# Empty_Shield-v13.net
KiCad netlist of a schematic drawn in EAGLE
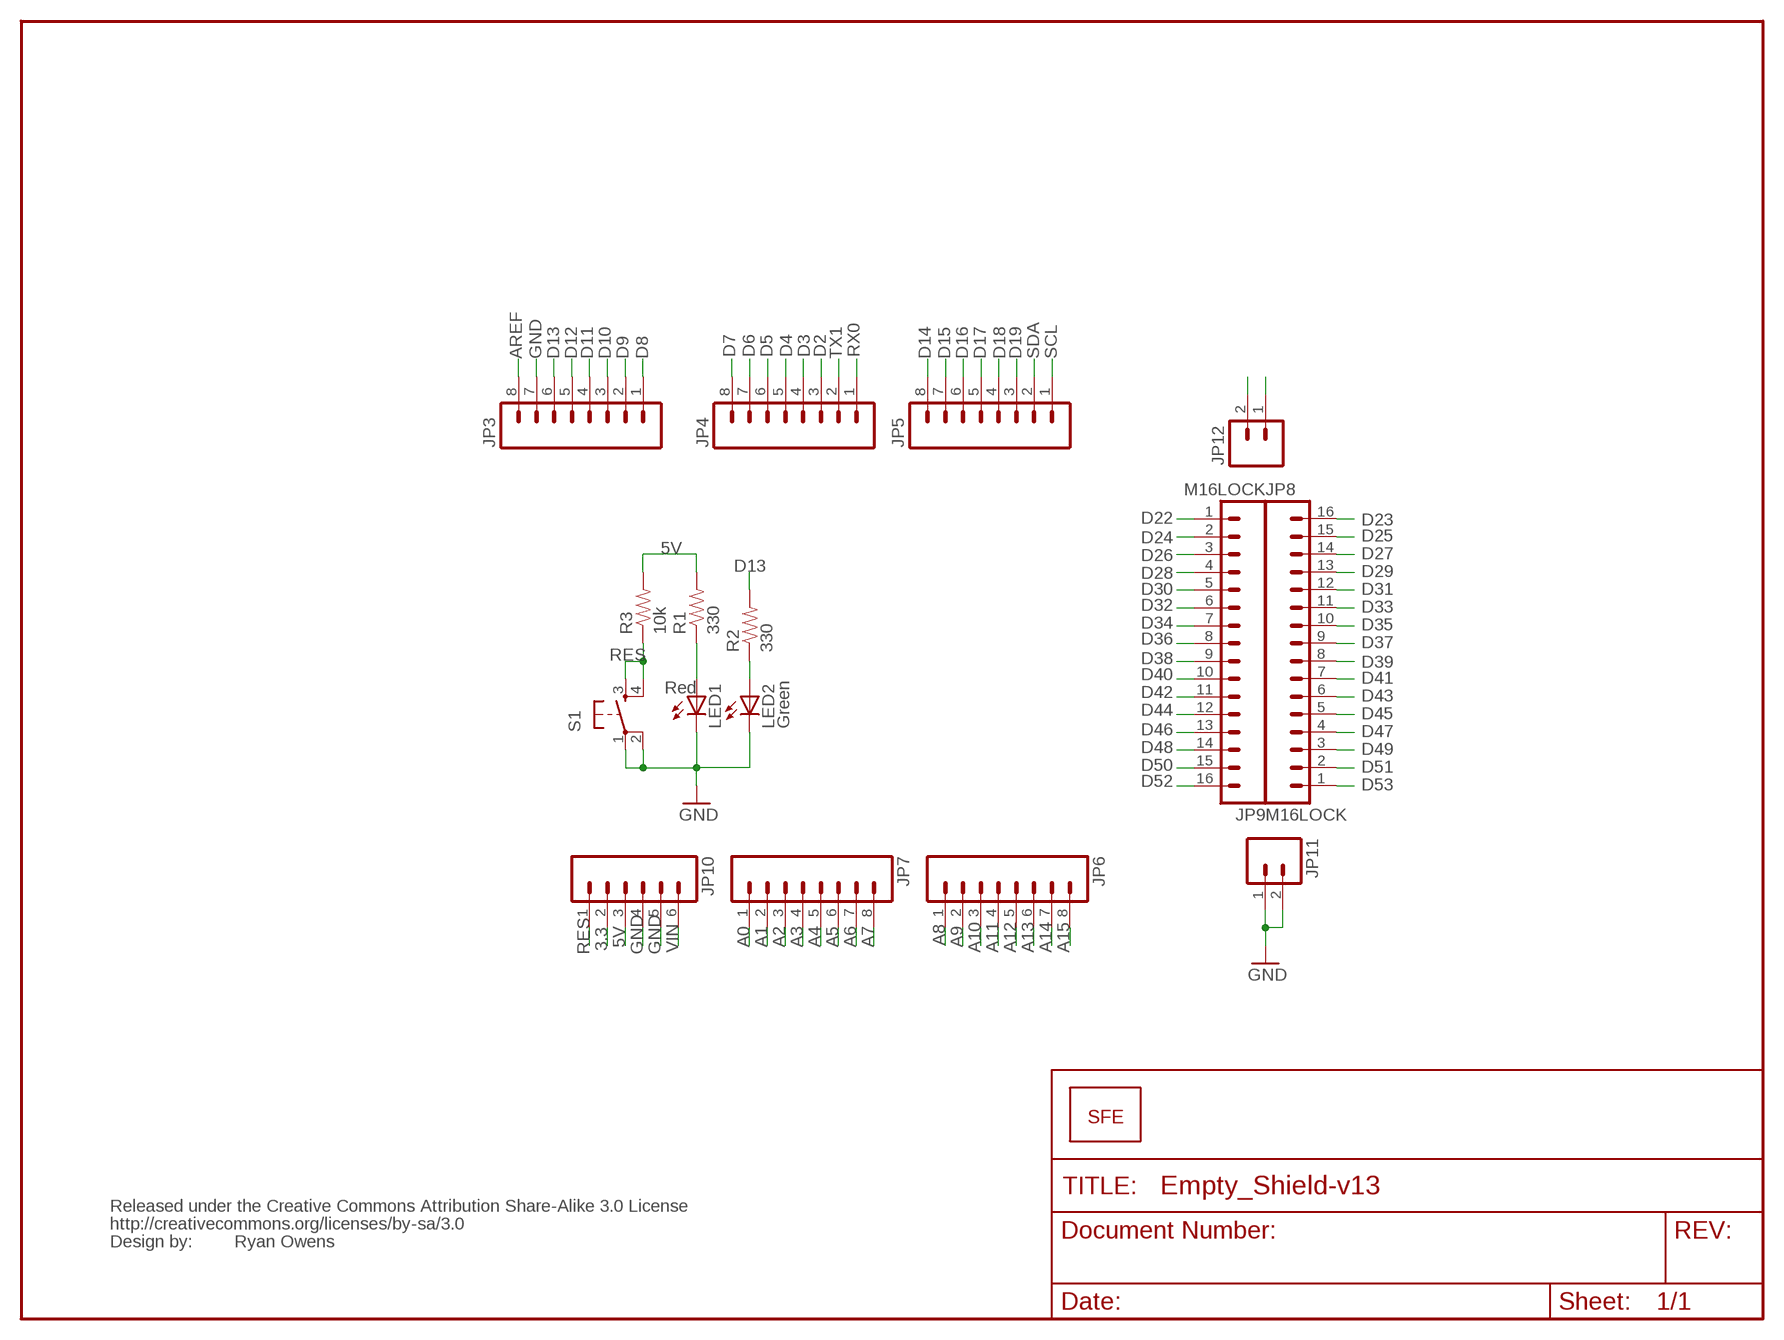
[diagram p0: schematic, sheet 1]

(export (version "E")
  (design (tool "Eeschema 10.0.6"))
  (components
    (comp (ref "JP3")
      (value "M08LOCK")
      (footprint "eagle-import:1X08_LOCK")
      (libsource (lib "eagle-import") (part "M08LOCK"))
    )
    (comp (ref "JP4")
      (value "M08LOCK")
      (footprint "eagle-import:1X08_LOCK")
      (libsource (lib "eagle-import") (part "M08LOCK"))
    )
    (comp (ref "JP5")
      (value "M08LOCK")
      (footprint "eagle-import:1X08_LOCK")
      (libsource (lib "eagle-import") (part "M08LOCK"))
    )
    (comp (ref "JP6")
      (value "M08LOCK")
      (footprint "eagle-import:1X08_LOCK")
      (libsource (lib "eagle-import") (part "M08LOCK"))
    )
    (comp (ref "JP7")
      (value "M08LOCK")
      (footprint "eagle-import:1X08_LOCK")
      (libsource (lib "eagle-import") (part "M08LOCK"))
    )
    (comp (ref "JP8")
      (value "M16LOCK")
      (footprint "eagle-import:1X16_LOCK")
      (libsource (lib "eagle-import") (part "M16LOCK"))
    )
    (comp (ref "JP9")
      (value "M16LOCK")
      (footprint "eagle-import:1X16_LOCK")
      (libsource (lib "eagle-import") (part "M16LOCK"))
    )
    (comp (ref "JP10")
      (value "M06LOCK")
      (footprint "eagle-import:1X06_LOCK")
      (libsource (lib "eagle-import") (part "M06LOCK"))
    )
    (comp (ref "JP11")
      (value "M02LOCK")
      (footprint "eagle-import:1X02_LOCK")
      (libsource (lib "eagle-import") (part "M02LOCK"))
    )
    (comp (ref "JP12")
      (value "M02LOCK")
      (footprint "eagle-import:1X02_LOCK")
      (libsource (lib "eagle-import") (part "M02LOCK"))
    )
    (comp (ref "LED1")
      (value "Red")
      (footprint "eagle-import:LED5MM")
      (libsource (lib "eagle-import") (part "LED5MM"))
    )
    (comp (ref "LED2")
      (value "Green")
      (footprint "eagle-import:LED5MM")
      (libsource (lib "eagle-import") (part "LED5MM"))
    )
    (comp (ref "R1")
      (value "330")
      (footprint "eagle-import:AXIAL-0.3")
      (libsource (lib "eagle-import") (part "RESISTORPTH1"))
    )
    (comp (ref "R2")
      (value "330")
      (footprint "eagle-import:AXIAL-0.3")
      (libsource (lib "eagle-import") (part "RESISTORPTH1"))
    )
    (comp (ref "R3")
      (value "10k")
      (footprint "eagle-import:AXIAL-0.3")
      (libsource (lib "eagle-import") (part "RESISTORPTH1"))
    )
    (comp (ref "S1")
      (value "TAC_SWITCHPTH")
      (footprint "eagle-import:TACTILE-PTH")
      (libsource (lib "eagle-import") (part "TAC_SWITCHPTH"))
    )
    (comp (ref "U$1")
      (value "LOGO-SFENEW")
      (footprint "eagle-import:SFE-NEW-WEBLOGO")
      (libsource (lib "eagle-import") (part "LOGO-SFENEW"))
    )
    (comp (ref "U$2")
      (value "CREATIVE_COMMONS")
      (footprint "eagle-import:CREATIVE_COMMONS")
      (libsource (lib "eagle-import") (part "CREATIVE_COMMONS"))
    )
  )
  (nets
    (net (code "1") (name "/3.3") (class "Default")
      (node (ref "JP10") (pin "2") (pinfunction "2_2") (pintype "passive"))
    )
    (net (code "2") (name "/5V") (class "Default")
      (node (ref "JP10") (pin "3") (pinfunction "3_3") (pintype "passive"))
      (node (ref "R1") (pin "P$2") (pinfunction "2_P$2") (pintype "passive"))
      (node (ref "R3") (pin "P$2") (pinfunction "2_P$2") (pintype "passive"))
    )
    (net (code "3") (name "/5V@1") (class "Default")
      (node (ref "JP12") (pin "1") (pinfunction "1_1") (pintype "passive"))
      (node (ref "JP12") (pin "2") (pinfunction "2_2") (pintype "passive"))
    )
    (net (code "4") (name "/A0") (class "Default")
      (node (ref "JP7") (pin "1") (pinfunction "1_1") (pintype "passive"))
    )
    (net (code "5") (name "/A1") (class "Default")
      (node (ref "JP7") (pin "2") (pinfunction "2_2") (pintype "passive"))
    )
    (net (code "6") (name "/A2") (class "Default")
      (node (ref "JP7") (pin "3") (pinfunction "3_3") (pintype "passive"))
    )
    (net (code "7") (name "/A3") (class "Default")
      (node (ref "JP7") (pin "4") (pinfunction "4_4") (pintype "passive"))
    )
    (net (code "8") (name "/A4") (class "Default")
      (node (ref "JP7") (pin "5") (pinfunction "5_5") (pintype "passive"))
    )
    (net (code "9") (name "/A5") (class "Default")
      (node (ref "JP7") (pin "6") (pinfunction "6_6") (pintype "passive"))
    )
    (net (code "10") (name "/A6") (class "Default")
      (node (ref "JP7") (pin "7") (pinfunction "7_7") (pintype "passive"))
    )
    (net (code "11") (name "/A7") (class "Default")
      (node (ref "JP7") (pin "8") (pinfunction "8_8") (pintype "passive"))
    )
    (net (code "12") (name "/A8") (class "Default")
      (node (ref "JP6") (pin "1") (pinfunction "1_1") (pintype "passive"))
    )
    (net (code "13") (name "/A9") (class "Default")
      (node (ref "JP6") (pin "2") (pinfunction "2_2") (pintype "passive"))
    )
    (net (code "14") (name "/A10") (class "Default")
      (node (ref "JP6") (pin "3") (pinfunction "3_3") (pintype "passive"))
    )
    (net (code "15") (name "/A11") (class "Default")
      (node (ref "JP6") (pin "4") (pinfunction "4_4") (pintype "passive"))
    )
    (net (code "16") (name "/A12") (class "Default")
      (node (ref "JP6") (pin "5") (pinfunction "5_5") (pintype "passive"))
    )
    (net (code "17") (name "/A13") (class "Default")
      (node (ref "JP6") (pin "6") (pinfunction "6_6") (pintype "passive"))
    )
    (net (code "18") (name "/A14") (class "Default")
      (node (ref "JP6") (pin "7") (pinfunction "7_7") (pintype "passive"))
    )
    (net (code "19") (name "/A15") (class "Default")
      (node (ref "JP6") (pin "8") (pinfunction "8_8") (pintype "passive"))
    )
    (net (code "20") (name "/AREF") (class "Default")
      (node (ref "JP3") (pin "8") (pinfunction "8_8") (pintype "passive"))
    )
    (net (code "21") (name "/D2") (class "Default")
      (node (ref "JP4") (pin "3") (pinfunction "3_3") (pintype "passive"))
    )
    (net (code "22") (name "/D3") (class "Default")
      (node (ref "JP4") (pin "4") (pinfunction "4_4") (pintype "passive"))
    )
    (net (code "23") (name "/D4") (class "Default")
      (node (ref "JP4") (pin "5") (pinfunction "5_5") (pintype "passive"))
    )
    (net (code "24") (name "/D5") (class "Default")
      (node (ref "JP4") (pin "6") (pinfunction "6_6") (pintype "passive"))
    )
    (net (code "25") (name "/D6") (class "Default")
      (node (ref "JP4") (pin "7") (pinfunction "7_7") (pintype "passive"))
    )
    (net (code "26") (name "/D7") (class "Default")
      (node (ref "JP4") (pin "8") (pinfunction "8_8") (pintype "passive"))
    )
    (net (code "27") (name "/D8") (class "Default")
      (node (ref "JP3") (pin "1") (pinfunction "1_1") (pintype "passive"))
    )
    (net (code "28") (name "/D9") (class "Default")
      (node (ref "JP3") (pin "2") (pinfunction "2_2") (pintype "passive"))
    )
    (net (code "29") (name "/D10") (class "Default")
      (node (ref "JP3") (pin "3") (pinfunction "3_3") (pintype "passive"))
    )
    (net (code "30") (name "/D11") (class "Default")
      (node (ref "JP3") (pin "4") (pinfunction "4_4") (pintype "passive"))
    )
    (net (code "31") (name "/D12") (class "Default")
      (node (ref "JP3") (pin "5") (pinfunction "5_5") (pintype "passive"))
    )
    (net (code "32") (name "/D13") (class "Default")
      (node (ref "JP3") (pin "6") (pinfunction "6_6") (pintype "passive"))
      (node (ref "R2") (pin "P$2") (pinfunction "2_P$2") (pintype "passive"))
    )
    (net (code "33") (name "/D14") (class "Default")
      (node (ref "JP5") (pin "8") (pinfunction "8_8") (pintype "passive"))
    )
    (net (code "34") (name "/D15") (class "Default")
      (node (ref "JP5") (pin "7") (pinfunction "7_7") (pintype "passive"))
    )
    (net (code "35") (name "/D16") (class "Default")
      (node (ref "JP5") (pin "6") (pinfunction "6_6") (pintype "passive"))
    )
    (net (code "36") (name "/D17") (class "Default")
      (node (ref "JP5") (pin "5") (pinfunction "5_5") (pintype "passive"))
    )
    (net (code "37") (name "/D18") (class "Default")
      (node (ref "JP5") (pin "4") (pinfunction "4_4") (pintype "passive"))
    )
    (net (code "38") (name "/D19") (class "Default")
      (node (ref "JP5") (pin "3") (pinfunction "3_3") (pintype "passive"))
    )
    (net (code "39") (name "/D22") (class "Default")
      (node (ref "JP9") (pin "1") (pinfunction "1_1") (pintype "passive"))
    )
    (net (code "40") (name "/D23") (class "Default")
      (node (ref "JP8") (pin "16") (pinfunction "16_16") (pintype "passive"))
    )
    (net (code "41") (name "/D24") (class "Default")
      (node (ref "JP9") (pin "2") (pinfunction "2_2") (pintype "passive"))
    )
    (net (code "42") (name "/D25") (class "Default")
      (node (ref "JP8") (pin "15") (pinfunction "15_15") (pintype "passive"))
    )
    (net (code "43") (name "/D26") (class "Default")
      (node (ref "JP9") (pin "3") (pinfunction "3_3") (pintype "passive"))
    )
    (net (code "44") (name "/D27") (class "Default")
      (node (ref "JP8") (pin "14") (pinfunction "14_14") (pintype "passive"))
    )
    (net (code "45") (name "/D28") (class "Default")
      (node (ref "JP9") (pin "4") (pinfunction "4_4") (pintype "passive"))
    )
    (net (code "46") (name "/D29") (class "Default")
      (node (ref "JP8") (pin "13") (pinfunction "13_13") (pintype "passive"))
    )
    (net (code "47") (name "/D30") (class "Default")
      (node (ref "JP9") (pin "5") (pinfunction "5_5") (pintype "passive"))
    )
    (net (code "48") (name "/D31") (class "Default")
      (node (ref "JP8") (pin "12") (pinfunction "12_12") (pintype "passive"))
    )
    (net (code "49") (name "/D32") (class "Default")
      (node (ref "JP9") (pin "6") (pinfunction "6_6") (pintype "passive"))
    )
    (net (code "50") (name "/D33") (class "Default")
      (node (ref "JP8") (pin "11") (pinfunction "11_11") (pintype "passive"))
    )
    (net (code "51") (name "/D34") (class "Default")
      (node (ref "JP9") (pin "7") (pinfunction "7_7") (pintype "passive"))
    )
    (net (code "52") (name "/D35") (class "Default")
      (node (ref "JP8") (pin "10") (pinfunction "10_10") (pintype "passive"))
    )
    (net (code "53") (name "/D36") (class "Default")
      (node (ref "JP9") (pin "8") (pinfunction "8_8") (pintype "passive"))
    )
    (net (code "54") (name "/D37") (class "Default")
      (node (ref "JP8") (pin "9") (pinfunction "9_9") (pintype "passive"))
    )
    (net (code "55") (name "/D38") (class "Default")
      (node (ref "JP9") (pin "9") (pinfunction "9_9") (pintype "passive"))
    )
    (net (code "56") (name "/D39") (class "Default")
      (node (ref "JP8") (pin "8") (pinfunction "8_8") (pintype "passive"))
    )
    (net (code "57") (name "/D40") (class "Default")
      (node (ref "JP9") (pin "10") (pinfunction "10_10") (pintype "passive"))
    )
    (net (code "58") (name "/D41") (class "Default")
      (node (ref "JP8") (pin "7") (pinfunction "7_7") (pintype "passive"))
    )
    (net (code "59") (name "/D42") (class "Default")
      (node (ref "JP9") (pin "11") (pinfunction "11_11") (pintype "passive"))
    )
    (net (code "60") (name "/D43") (class "Default")
      (node (ref "JP8") (pin "6") (pinfunction "6_6") (pintype "passive"))
    )
    (net (code "61") (name "/D44") (class "Default")
      (node (ref "JP9") (pin "12") (pinfunction "12_12") (pintype "passive"))
    )
    (net (code "62") (name "/D45") (class "Default")
      (node (ref "JP8") (pin "5") (pinfunction "5_5") (pintype "passive"))
    )
    (net (code "63") (name "/D46") (class "Default")
      (node (ref "JP9") (pin "13") (pinfunction "13_13") (pintype "passive"))
    )
    (net (code "64") (name "/D47") (class "Default")
      (node (ref "JP8") (pin "4") (pinfunction "4_4") (pintype "passive"))
    )
    (net (code "65") (name "/D48") (class "Default")
      (node (ref "JP9") (pin "14") (pinfunction "14_14") (pintype "passive"))
    )
    (net (code "66") (name "/D49") (class "Default")
      (node (ref "JP8") (pin "3") (pinfunction "3_3") (pintype "passive"))
    )
    (net (code "67") (name "/D50") (class "Default")
      (node (ref "JP9") (pin "15") (pinfunction "15_15") (pintype "passive"))
    )
    (net (code "68") (name "/D51") (class "Default")
      (node (ref "JP8") (pin "2") (pinfunction "2_2") (pintype "passive"))
    )
    (net (code "69") (name "/D52") (class "Default")
      (node (ref "JP9") (pin "16") (pinfunction "16_16") (pintype "passive"))
    )
    (net (code "70") (name "/D53") (class "Default")
      (node (ref "JP8") (pin "1") (pinfunction "1_1") (pintype "passive"))
    )
    (net (code "71") (name "/RES") (class "Default")
      (node (ref "JP10") (pin "1") (pinfunction "1_1") (pintype "passive"))
      (node (ref "R3") (pin "P$1") (pinfunction "1_P$1") (pintype "passive"))
      (node (ref "S1") (pin "3") (pinfunction "3_3") (pintype "passive"))
      (node (ref "S1") (pin "4") (pinfunction "4_4") (pintype "passive"))
    )
    (net (code "72") (name "/RX0") (class "Default")
      (node (ref "JP4") (pin "1") (pinfunction "1_1") (pintype "passive"))
    )
    (net (code "73") (name "/SCL") (class "Default")
      (node (ref "JP5") (pin "1") (pinfunction "1_1") (pintype "passive"))
    )
    (net (code "74") (name "/SDA") (class "Default")
      (node (ref "JP5") (pin "2") (pinfunction "2_2") (pintype "passive"))
    )
    (net (code "75") (name "/TX1") (class "Default")
      (node (ref "JP4") (pin "2") (pinfunction "2_2") (pintype "passive"))
    )
    (net (code "76") (name "/VIN") (class "Default")
      (node (ref "JP10") (pin "6") (pinfunction "6_6") (pintype "passive"))
    )
    (net (code "77") (name "GND") (class "Default")
      (node (ref "JP10") (pin "4") (pinfunction "4_4") (pintype "passive"))
      (node (ref "JP10") (pin "5") (pinfunction "5_5") (pintype "passive"))
      (node (ref "JP11") (pin "1") (pinfunction "1_1") (pintype "passive"))
      (node (ref "JP11") (pin "2") (pinfunction "2_2") (pintype "passive"))
      (node (ref "JP3") (pin "7") (pinfunction "7_7") (pintype "passive"))
      (node (ref "LED1") (pin "K") (pinfunction "C_K") (pintype "passive"))
      (node (ref "LED2") (pin "K") (pinfunction "C_K") (pintype "passive"))
      (node (ref "S1") (pin "1") (pinfunction "1_1") (pintype "passive"))
      (node (ref "S1") (pin "2") (pinfunction "2_2") (pintype "passive"))
    )
    (net (code "78") (name "Net-(R1-1)") (class "Default")
      (node (ref "LED1") (pin "A") (pinfunction "A_A") (pintype "passive"))
      (node (ref "R1") (pin "P$1") (pinfunction "1_P$1") (pintype "passive"))
    )
    (net (code "79") (name "Net-(R2-1)") (class "Default")
      (node (ref "LED2") (pin "A") (pinfunction "A_A") (pintype "passive"))
      (node (ref "R2") (pin "P$1") (pinfunction "1_P$1") (pintype "passive"))
    )
  )
)
